# hexcooler_v2.net
KiCad netlist of a schematic drawn in EasyEDA Pro
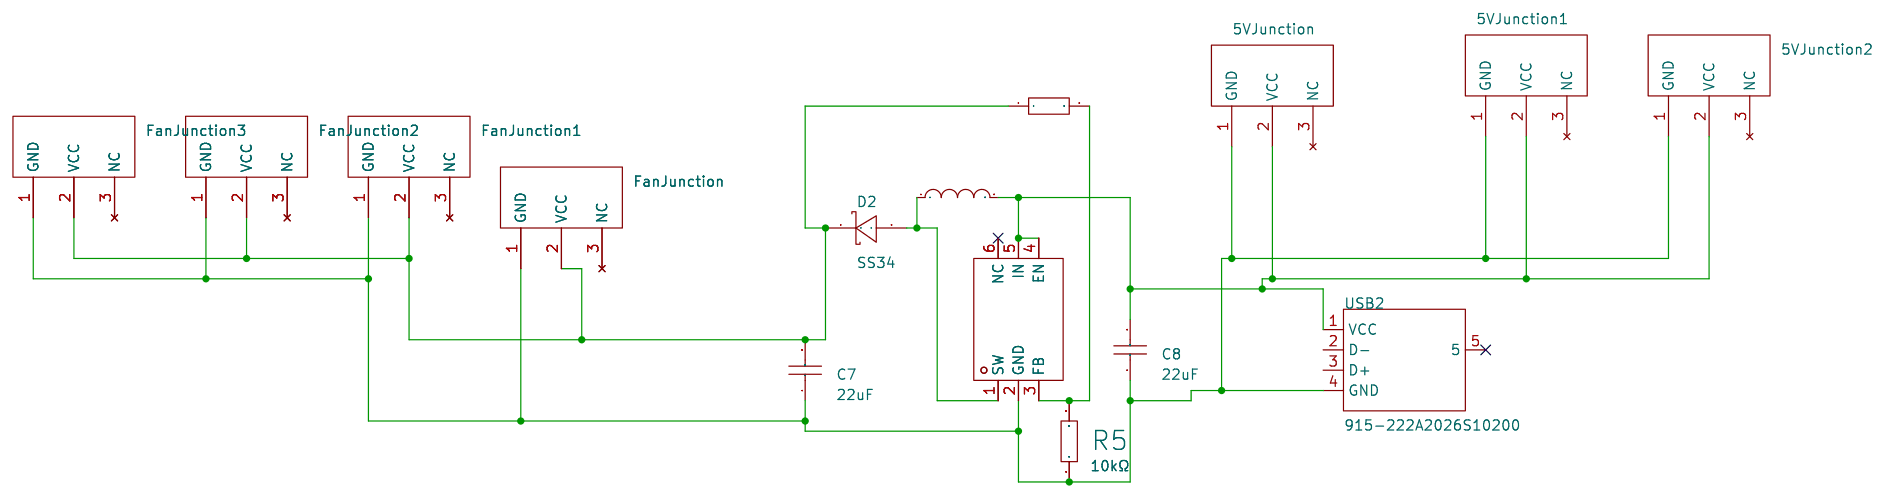
[diagram p0: schematic sheet]

(export (version "E")
  (design (tool "Eeschema 10.0.6"))
  (components
    (comp (ref "5VJunction")
      (value "~")
      (footprint "easyedapro:pads junction")
      (libsource (lib "easyedapro") (part "connector for m y fan"))
    )
    (comp (ref "5VJunction1")
      (value "~")
      (footprint "easyedapro:pads junction")
      (libsource (lib "easyedapro") (part "connector for m y fan"))
    )
    (comp (ref "5VJunction2")
      (value "~")
      (footprint "easyedapro:pads junction")
      (libsource (lib "easyedapro") (part "connector for m y fan"))
    )
    (comp (ref "C7")
      (value "22uF")
      (footprint "easyedapro:C1206")
      (description "Capacitance:22uF Tolerance:±10% Tolerance:±10% Voltage Rating:25V Temperature Coefficient:X5R")
      (fields
        (field (name "Manufacturer Part") "CL31A226KAHNNNE")
        (field (name "Manufacturer") "SAMSUNG(三星)")
      )
      (libsource (lib "easyedapro") (part "CL31A226KAHNNNE"))
    )
    (comp (ref "C8")
      (value "22uF")
      (footprint "easyedapro:C1206")
      (description "Capacitance:22uF Tolerance:±10% Tolerance:±10% Voltage Rating:25V Temperature Coefficient:X5R")
      (fields
        (field (name "Manufacturer Part") "CL31A226KAHNNNE")
        (field (name "Manufacturer") "SAMSUNG(三星)")
      )
      (libsource (lib "easyedapro") (part "CL31A226KAHNNNE"))
    )
    (comp (ref "D2")
      (value "SS34")
      (footprint "easyedapro:SMA_L4.3-W2.6-LS5.2-RD")
      (fields (field (name "Manufacturer") "MDD(辰达半导体)"))
      (libsource (lib "easyedapro") (part "SS34_C8678"))
    )
    (comp (ref "FanJunction")
      (value "~")
      (footprint "easyedapro:pads junction")
      (libsource (lib "easyedapro") (part "connector for m y fan"))
    )
    (comp (ref "FanJunction1")
      (value "~")
      (footprint "easyedapro:pads junction")
      (libsource (lib "easyedapro") (part "connector for m y fan"))
    )
    (comp (ref "FanJunction2")
      (value "~")
      (footprint "easyedapro:pads junction")
      (libsource (lib "easyedapro") (part "connector for m y fan"))
    )
    (comp (ref "FanJunction3")
      (value "~")
      (footprint "easyedapro:pads junction")
      (libsource (lib "easyedapro") (part "connector for m y fan"))
    )
    (comp (ref "L1")
      (value "4.7uH")
      (footprint "easyedapro:IND-SMD_L3.0-W3.0_LQH3NPN2R2NG0L")
      (fields (field (name "Manufacturer Part") "LQH3NPN4R7MJRL") (field (name "Manufacturer") "muRata(村田)"))
      (libsource (lib "easyedapro") (part "LQH3NPN4R7MJRL"))
    )
    (comp (ref "R3")
      (value "200kΩ")
      (footprint "easyedapro:R0805")
      (fields
        (field (name "Manufacturer Part") "0805W8F2003T5E")
        (field (name "Manufacturer") "UNI-ROYAL(厚声)")
      )
      (libsource (lib "easyedapro") (part "0805W8F2003T5E"))
    )
    (comp (ref "R5")
      (value "10kΩ")
      (footprint "easyedapro:R0603")
      (fields
        (field (name "Manufacturer Part") "0603WAF1002T5E")
        (field (name "Manufacturer") "UNI-ROYAL(厚声)")
      )
      (libsource (lib "easyedapro") (part "0603WAF1002T5E"))
    )
    (comp (ref "U3")
      (value "MT3608")
      (footprint "easyedapro:SOT-23-6_L2.9-W1.6-P0.95-LS2.8-BL")
      (fields (field (name "Manufacturer") "西安航天民芯"))
      (libsource (lib "easyedapro") (part "MT3608"))
    )
    (comp (ref "USB2")
      (value "915-222A2026S10200")
      (footprint "easyedapro:USB-A-SMD_915-222A2026S10200")
      (fields (field (name "Manufacturer") "精拓金"))
      (libsource (lib "easyedapro") (part "915-222A2026S10200"))
    )
  )
  (nets
    (net (code "1") (name "Net-(5VJunction-GND)") (class "Default")
      (node (ref "5VJunction") (pin "1") (pinfunction "GND_1") (pintype "input"))
      (node (ref "5VJunction1") (pin "1") (pinfunction "GND_1") (pintype "input"))
      (node (ref "5VJunction2") (pin "1") (pinfunction "GND_1") (pintype "input"))
      (node (ref "C7") (pin "1") (pinfunction "1_1") (pintype "input"))
      (node (ref "C8") (pin "1") (pinfunction "1_1") (pintype "input"))
      (node (ref "FanJunction") (pin "1") (pinfunction "GND_1") (pintype "input"))
      (node (ref "FanJunction1") (pin "1") (pinfunction "GND_1") (pintype "input"))
      (node (ref "FanJunction2") (pin "1") (pinfunction "GND_1") (pintype "input"))
      (node (ref "FanJunction3") (pin "1") (pinfunction "GND_1") (pintype "input"))
      (node (ref "R5") (pin "1") (pinfunction "1_1") (pintype "input"))
      (node (ref "U3") (pin "2") (pinfunction "GND_2") (pintype "unspecified"))
      (node (ref "USB2") (pin "4") (pinfunction "GND_4") (pintype "unspecified"))
    )
    (net (code "2") (name "Net-(5VJunction-VCC)") (class "Default")
      (node (ref "5VJunction") (pin "2") (pinfunction "VCC_2") (pintype "input"))
      (node (ref "5VJunction1") (pin "2") (pinfunction "VCC_2") (pintype "input"))
      (node (ref "5VJunction2") (pin "2") (pinfunction "VCC_2") (pintype "input"))
      (node (ref "C8") (pin "2") (pinfunction "2_2") (pintype "input"))
      (node (ref "L1") (pin "2") (pinfunction "2_2") (pintype "unspecified"))
      (node (ref "U3") (pin "4") (pinfunction "EN_4") (pintype "unspecified"))
      (node (ref "U3") (pin "5") (pinfunction "IN_5") (pintype "unspecified"))
      (node (ref "USB2") (pin "1") (pinfunction "VCC_1") (pintype "unspecified"))
    )
    (net (code "3") (name "Net-(D2-A)") (class "Default")
      (node (ref "D2") (pin "2") (pinfunction "A_2") (pintype "unspecified"))
      (node (ref "L1") (pin "1") (pinfunction "1_1") (pintype "unspecified"))
      (node (ref "U3") (pin "1") (pinfunction "SW_1") (pintype "unspecified"))
    )
    (net (code "4") (name "Net-(D2-K)") (class "Default")
      (node (ref "C7") (pin "2") (pinfunction "2_2") (pintype "input"))
      (node (ref "D2") (pin "1") (pinfunction "K_1") (pintype "unspecified"))
      (node (ref "FanJunction") (pin "2") (pinfunction "VCC_2") (pintype "input"))
      (node (ref "FanJunction1") (pin "2") (pinfunction "VCC_2") (pintype "input"))
      (node (ref "FanJunction2") (pin "2") (pinfunction "VCC_2") (pintype "input"))
      (node (ref "FanJunction3") (pin "2") (pinfunction "VCC_2") (pintype "input"))
      (node (ref "R3") (pin "1") (pinfunction "1_1") (pintype "input"))
    )
    (net (code "5") (name "Net-(U3-FB)") (class "Default")
      (node (ref "R3") (pin "2") (pinfunction "2_2") (pintype "input"))
      (node (ref "R5") (pin "2") (pinfunction "2_2") (pintype "input"))
      (node (ref "U3") (pin "3") (pinfunction "FB_3") (pintype "unspecified"))
    )
    (net (code "6") (name "unconnected-(5VJunction-NC-Pad3)") (class "Default")
      (node (ref "5VJunction") (pin "3") (pinfunction "NC_3") (pintype "no_connect"))
    )
    (net (code "7") (name "unconnected-(5VJunction1-NC-Pad3)") (class "Default")
      (node (ref "5VJunction1") (pin "3") (pinfunction "NC_3") (pintype "no_connect"))
    )
    (net (code "8") (name "unconnected-(5VJunction2-NC-Pad3)") (class "Default")
      (node (ref "5VJunction2") (pin "3") (pinfunction "NC_3") (pintype "no_connect"))
    )
    (net (code "9") (name "unconnected-(FanJunction-NC-Pad3)") (class "Default")
      (node (ref "FanJunction") (pin "3") (pinfunction "NC_3") (pintype "no_connect"))
    )
    (net (code "10") (name "unconnected-(FanJunction1-NC-Pad3)") (class "Default")
      (node (ref "FanJunction1") (pin "3") (pinfunction "NC_3") (pintype "no_connect"))
    )
    (net (code "11") (name "unconnected-(FanJunction2-NC-Pad3)") (class "Default")
      (node (ref "FanJunction2") (pin "3") (pinfunction "NC_3") (pintype "no_connect"))
    )
    (net (code "12") (name "unconnected-(FanJunction3-NC-Pad3)") (class "Default")
      (node (ref "FanJunction3") (pin "3") (pinfunction "NC_3") (pintype "no_connect"))
    )
    (net (code "13") (name "unconnected-(U3-NC-Pad6)") (class "Default")
      (node (ref "U3") (pin "6") (pinfunction "NC_6") (pintype "unspecified+no_connect"))
    )
    (net (code "14") (name "unconnected-(USB2-D+-Pad3)") (class "Default")
      (node (ref "USB2") (pin "3") (pinfunction "D+_3") (pintype "unspecified"))
    )
    (net (code "15") (name "unconnected-(USB2-D--Pad2)") (class "Default")
      (node (ref "USB2") (pin "2") (pinfunction "D-_2") (pintype "unspecified"))
    )
    (net (code "16") (name "unconnected-(USB2-Pad5)") (class "Default")
      (node (ref "USB2") (pin "5") (pinfunction "5_5") (pintype "unspecified+no_connect"))
    )
  )
)
